# PicoInterface.net
KiCad netlist of a schematic drawn in Altium Designer
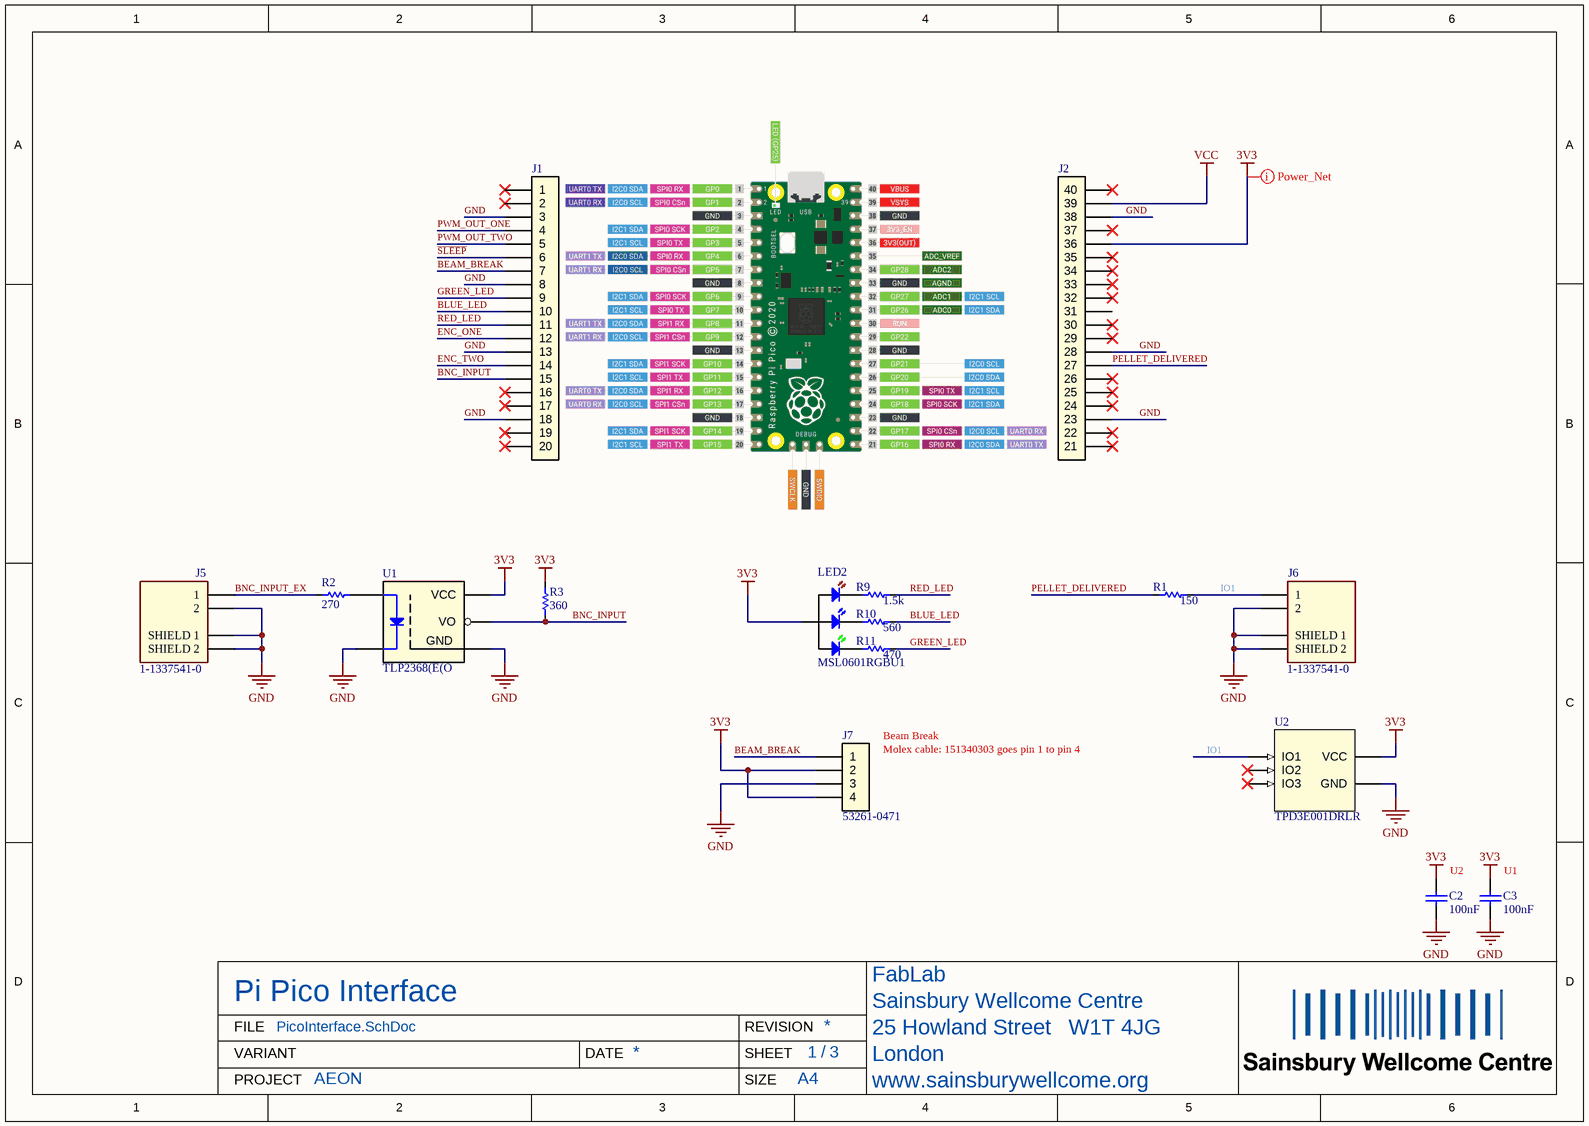
[diagram p0: PicoInterface.SchDoc]

(export (version "E")
  (design (tool "Eeschema 10.0.6"))
  (components
    (comp (ref "C2")
      (value "100nF")
      (footprint "FP-GRM188-0_1-e0_2_0_5-IPC_B")
      (description "0.1µF ±10% 100V Ceramic Capacitor X7R 0603 (1608 Metric)")
      (fields (field (name "VOLTAGE") "100V") (field (name "TOLERANCE") "10%"))
      (libsource (lib "Sainsbury Wellcome Centre") (part "Cap"))
    )
    (comp (ref "C3")
      (value "100nF")
      (footprint "FP-GRM188-0_1-e0_2_0_5-IPC_B")
      (description "0.1µF ±10% 100V Ceramic Capacitor X7R 0603 (1608 Metric)")
      (fields (field (name "VOLTAGE") "100V") (field (name "TOLERANCE") "10%"))
      (libsource (lib "Sainsbury Wellcome Centre") (part "Cap"))
    )
    (comp (ref "J1")
      (value "SSW-120-01-x-S")
      (footprint "SAMTEC_SSW-120-01-G-S")
      (description "Conn Socket Strip SKT 20 POS 2.54mm Solder ST Thru-Hole")
      (libsource (lib "Sainsbury Wellcome Centre") (part "Jack 20x1"))
    )
    (comp (ref "J2")
      (value "SSW-120-01-x-S - 21-40")
      (footprint "SAMTEC_SSW-120-01-G-S - 21-40")
      (description "Conn Socket Strip SKT 20 POS 2.54mm Solder ST Thru-Hole (pins 21 - 40)")
      (libsource (lib "Sainsbury Wellcome Centre") (part "Jack 20x1 21-40"))
    )
    (comp (ref "J5")
      (value "1-1337541-0")
      (footprint "TE- 1-1337541-0")
      (fields (field (name "PARTNUMBER") "1-1337541-0"))
      (libsource (lib "Sainsbury Wellcome Centre") (part "TE-1-1337541-0"))
    )
    (comp (ref "J6")
      (value "1-1337541-0")
      (footprint "TE- 1-1337541-0")
      (fields (field (name "PARTNUMBER") "1-1337541-0"))
      (libsource (lib "") (part "TE-1-1337541-0_1"))
    )
    (comp (ref "J7")
      (value "53261-0471")
      (footprint "MOLEX_53261-0471")
      (description "MOLEX 1.25mm (.049\") Pitch PicoBlade Header, Surface Mount, Right Angle, Lead-free, 4 Circuits")
      (libsource (lib "Sainsbury Wellcome Centre") (part "Jack 4x1"))
    )
    (comp (ref "LED2")
      (value "MSL0601RGBU1")
      (footprint "LED_MSL06_ROM")
      (description "Triple Color LED, Red/green/blue, Milky White")
      (fields (field (name "PARTNUMBER") "MSL0601RGBU1"))
      (libsource (lib "Sainsbury Wellcome Centre") (part "LED-RGB"))
    )
    (comp (ref "R1")
      (value "150")
      (footprint "FP-CPF0603-IPC_B")
      (description "Surface Mount Resistor 150 Ohm 1/16 W 0.1% 0603 (1608 Metric)")
      (fields (field (name "TOLERANCE") "0.1%") (field (name "Comment") "R0603-150R-1/16W-0.1%"))
      (libsource (lib "Sainsbury Wellcome Centre") (part "Res"))
    )
    (comp (ref "R2")
      (value "270")
      (footprint "FP-CPF0603-IPC_B")
      (description "Surface Mount Resistor 270 Ohm 1/16 W 0.1% 0603 (1608 Metric)")
      (fields (field (name "TOLERANCE") "0.1%") (field (name "Comment") "R0603-270R-1/16W-0.1%"))
      (libsource (lib "Sainsbury Wellcome Centre") (part "Res"))
    )
    (comp (ref "R3")
      (value "360")
      (footprint "FP-CPF0603-IPC_B")
      (description "Surface Mount Resistor 360 Ohm 1/16 W 0.1% 0603 (1608 Metric)")
      (fields (field (name "TOLERANCE") "0.1%") (field (name "Comment") "R0603-360R-1/16W-0.1%"))
      (libsource (lib "Sainsbury Wellcome Centre") (part "Res"))
    )
    (comp (ref "R9")
      (value "1.5k")
      (footprint "FP-CPF0603-IPC_B")
      (description "Surface Mount Resistor 1k5 Ohm 1/16 W 0.1% 0603 (1608 Metric)")
      (fields (field (name "TOLERANCE") "0.1%") (field (name "Comment") "R0603-1k5-1/16W-0.1%"))
      (libsource (lib "Sainsbury Wellcome Centre") (part "Res"))
    )
    (comp (ref "R10")
      (value "560")
      (footprint "FP-CPF0603-IPC_B")
      (description "Surface Mount Resistor 560 Ohm 1/16 W 0.1% 0603 (1608 Metric)")
      (fields (field (name "TOLERANCE") "0.1%") (field (name "Comment") "R0603-560R-1/16W-0.1%"))
      (libsource (lib "Sainsbury Wellcome Centre") (part "Res"))
    )
    (comp (ref "R11")
      (value "470")
      (footprint "FP-CPF0603-IPC_B")
      (description "Surface Mount Resistor 470 Ohm 1/16 W 0.1% 0603 (1608 Metric)")
      (fields (field (name "TOLERANCE") "0.1%") (field (name "Comment") "R0603-470R-1/16W-0.1%"))
      (libsource (lib "Sainsbury Wellcome Centre") (part "Res"))
    )
    (comp (ref "U1")
      (value "TLP2368")
      (footprint "5pin SO6_TOS")
      (fields (field (name "PARTNUMBER") "TLP2368(E(O"))
      (libsource (lib "Sainsbury Wellcome Centre") (part "TOS-TLP2368"))
    )
    (comp (ref "U2")
      (value "TPD3E001DRLR")
      (footprint "DRL5_TEX")
      (description "Low-Capacitance 3-Channel +/-15KV ESD-Protection Array for High-Speed Data Interfaces 5-SOT-5X3")
      (fields (field (name "PARTNUMBER") "TPD3E001DRLR"))
      (libsource (lib "Sainsbury Wellcome Centre") (part "TPD3E001DRLR"))
    )
  )
  (nets
    (net (code "1") (name "/BEAM_BREAK") (class "Default")
      (node (ref "J1") (pin "7") (pinfunction "7_7") (pintype "passive"))
      (node (ref "J7") (pin "1") (pinfunction "1_1") (pintype "passive"))
    )
    (net (code "2") (name "/BLUE_LED") (class "Default")
      (node (ref "J1") (pin "10") (pinfunction "10_10") (pintype "passive"))
      (node (ref "R10") (pin "2") (pinfunction "2_2") (pintype "passive"))
    )
    (net (code "3") (name "/BNC_INPUT") (class "Default")
      (node (ref "J1") (pin "15") (pinfunction "15_15") (pintype "passive"))
      (node (ref "R3") (pin "1") (pinfunction "1_1") (pintype "passive"))
      (node (ref "U1") (pin "5") (pinfunction "VO_5") (pintype "open_collector"))
    )
    (net (code "4") (name "/BNC_INPUT_EX") (class "Default")
      (node (ref "J5") (pin "1") (pinfunction "1_1") (pintype "passive"))
      (node (ref "R2") (pin "1") (pinfunction "1_1") (pintype "passive"))
    )
    (net (code "5") (name "/ENC_ONE") (class "Default")
      (node (ref "J1") (pin "12") (pinfunction "12_12") (pintype "passive"))
    )
    (net (code "6") (name "/ENC_TWO") (class "Default")
      (node (ref "J1") (pin "14") (pinfunction "14_14") (pintype "passive"))
    )
    (net (code "7") (name "/GREEN_LED") (class "Default")
      (node (ref "J1") (pin "9") (pinfunction "9_9") (pintype "passive"))
      (node (ref "R11") (pin "2") (pinfunction "2_2") (pintype "passive"))
    )
    (net (code "8") (name "/IO1") (class "Default")
      (node (ref "J6") (pin "1") (pinfunction "1_1") (pintype "passive"))
      (node (ref "R1") (pin "2") (pinfunction "2_2") (pintype "passive"))
      (node (ref "U2") (pin "1") (pinfunction "IO1_1") (pintype "input"))
    )
    (net (code "9") (name "/PELLET_DELIVERED") (class "Default")
      (node (ref "J2") (pin "27") (pinfunction "27_27") (pintype "passive"))
      (node (ref "R1") (pin "1") (pinfunction "1_1") (pintype "passive"))
    )
    (net (code "10") (name "/PWM_OUT_ONE") (class "Default")
      (node (ref "J1") (pin "4") (pinfunction "4_4") (pintype "passive"))
    )
    (net (code "11") (name "/PWM_OUT_TWO") (class "Default")
      (node (ref "J1") (pin "5") (pinfunction "5_5") (pintype "passive"))
    )
    (net (code "12") (name "/RED_LED") (class "Default")
      (node (ref "J1") (pin "11") (pinfunction "11_11") (pintype "passive"))
      (node (ref "R9") (pin "2") (pinfunction "2_2") (pintype "passive"))
    )
    (net (code "13") (name "/SLEEP") (class "Default")
      (node (ref "J1") (pin "6") (pinfunction "6_6") (pintype "passive"))
    )
    (net (code "14") (name "3V3") (class "Default")
      (node (ref "C2") (pin "2") (pinfunction "2_2") (pintype "passive"))
      (node (ref "C3") (pin "2") (pinfunction "2_2") (pintype "passive"))
      (node (ref "J2") (pin "36") (pinfunction "36_36") (pintype "passive"))
      (node (ref "J7") (pin "2") (pinfunction "2_2") (pintype "passive"))
      (node (ref "J7") (pin "4") (pinfunction "4_4") (pintype "passive"))
      (node (ref "LED2") (pin "1") (pinfunction "1_1") (pintype "passive"))
      (node (ref "R3") (pin "2") (pinfunction "2_2") (pintype "passive"))
      (node (ref "U1") (pin "6") (pinfunction "VCC_6") (pintype "power_in"))
      (node (ref "U2") (pin "5") (pinfunction "VCC_5") (pintype "power_in"))
    )
    (net (code "15") (name "GND") (class "Default")
      (node (ref "C2") (pin "1") (pinfunction "1_1") (pintype "passive"))
      (node (ref "C3") (pin "1") (pinfunction "1_1") (pintype "passive"))
      (node (ref "J1") (pin "13") (pinfunction "13_13") (pintype "passive"))
      (node (ref "J1") (pin "18") (pinfunction "18_18") (pintype "passive"))
      (node (ref "J1") (pin "3") (pinfunction "3_3") (pintype "passive"))
      (node (ref "J1") (pin "8") (pinfunction "8_8") (pintype "passive"))
      (node (ref "J2") (pin "23") (pinfunction "23_23") (pintype "passive"))
      (node (ref "J2") (pin "28") (pinfunction "28_28") (pintype "passive"))
      (node (ref "J2") (pin "38") (pinfunction "38_38") (pintype "passive"))
      (node (ref "J5") (pin "2") (pinfunction "2_2") (pintype "passive"))
      (node (ref "J5") (pin "SH1") (pinfunction "SHIELD_1_SH1") (pintype "passive"))
      (node (ref "J5") (pin "SH2") (pinfunction "SHIELD_2_SH2") (pintype "passive"))
      (node (ref "J6") (pin "2") (pinfunction "2_2") (pintype "passive"))
      (node (ref "J6") (pin "SH1") (pinfunction "SHIELD_1_SH1") (pintype "passive"))
      (node (ref "J6") (pin "SH2") (pinfunction "SHIELD_2_SH2") (pintype "passive"))
      (node (ref "J7") (pin "3") (pinfunction "3_3") (pintype "passive"))
      (node (ref "U1") (pin "3") (pinfunction "CATHODE_3") (pintype "passive"))
      (node (ref "U1") (pin "4") (pinfunction "GND_4") (pintype "passive"))
      (node (ref "U2") (pin "3") (pinfunction "GND_3") (pintype "power_in"))
    )
    (net (code "16") (name "Net-(LED2-Pad2)") (class "Default")
      (node (ref "LED2") (pin "2") (pinfunction "2_2") (pintype "passive"))
      (node (ref "R11") (pin "1") (pinfunction "1_1") (pintype "passive"))
    )
    (net (code "17") (name "Net-(LED2-Pad3)") (class "Default")
      (node (ref "LED2") (pin "3") (pinfunction "3_3") (pintype "passive"))
      (node (ref "R10") (pin "1") (pinfunction "1_1") (pintype "passive"))
    )
    (net (code "18") (name "Net-(LED2-Pad4)") (class "Default")
      (node (ref "LED2") (pin "4") (pinfunction "4_4") (pintype "passive"))
      (node (ref "R9") (pin "1") (pinfunction "1_1") (pintype "passive"))
    )
    (net (code "19") (name "Net-(U1-ANODE)") (class "Default")
      (node (ref "R2") (pin "2") (pinfunction "2_2") (pintype "passive"))
      (node (ref "U1") (pin "1") (pinfunction "ANODE_1") (pintype "passive"))
    )
    (net (code "20") (name "VCC") (class "Default")
      (node (ref "J2") (pin "39") (pinfunction "39_39") (pintype "passive"))
    )
    (net (code "21") (name "unconnected-(J1-Pad1)") (class "Default")
      (node (ref "J1") (pin "1") (pinfunction "1_1") (pintype "passive+no_connect"))
    )
    (net (code "22") (name "unconnected-(J1-Pad2)") (class "Default")
      (node (ref "J1") (pin "2") (pinfunction "2_2") (pintype "passive+no_connect"))
    )
    (net (code "23") (name "unconnected-(J1-Pad16)") (class "Default")
      (node (ref "J1") (pin "16") (pinfunction "16_16") (pintype "passive+no_connect"))
    )
    (net (code "24") (name "unconnected-(J1-Pad17)") (class "Default")
      (node (ref "J1") (pin "17") (pinfunction "17_17") (pintype "passive+no_connect"))
    )
    (net (code "25") (name "unconnected-(J1-Pad19)") (class "Default")
      (node (ref "J1") (pin "19") (pinfunction "19_19") (pintype "passive+no_connect"))
    )
    (net (code "26") (name "unconnected-(J1-Pad20)") (class "Default")
      (node (ref "J1") (pin "20") (pinfunction "20_20") (pintype "passive+no_connect"))
    )
    (net (code "27") (name "unconnected-(J2-Pad21)") (class "Default")
      (node (ref "J2") (pin "21") (pinfunction "21_21") (pintype "passive+no_connect"))
    )
    (net (code "28") (name "unconnected-(J2-Pad22)") (class "Default")
      (node (ref "J2") (pin "22") (pinfunction "22_22") (pintype "passive+no_connect"))
    )
    (net (code "29") (name "unconnected-(J2-Pad24)") (class "Default")
      (node (ref "J2") (pin "24") (pinfunction "24_24") (pintype "passive+no_connect"))
    )
    (net (code "30") (name "unconnected-(J2-Pad25)") (class "Default")
      (node (ref "J2") (pin "25") (pinfunction "25_25") (pintype "passive+no_connect"))
    )
    (net (code "31") (name "unconnected-(J2-Pad26)") (class "Default")
      (node (ref "J2") (pin "26") (pinfunction "26_26") (pintype "passive+no_connect"))
    )
    (net (code "32") (name "unconnected-(J2-Pad29)") (class "Default")
      (node (ref "J2") (pin "29") (pinfunction "29_29") (pintype "passive+no_connect"))
    )
    (net (code "33") (name "unconnected-(J2-Pad30)") (class "Default")
      (node (ref "J2") (pin "30") (pinfunction "30_30") (pintype "passive+no_connect"))
    )
    (net (code "34") (name "unconnected-(J2-Pad31)") (class "Default")
      (node (ref "J2") (pin "31") (pinfunction "31_31") (pintype "passive"))
    )
    (net (code "35") (name "unconnected-(J2-Pad32)") (class "Default")
      (node (ref "J2") (pin "32") (pinfunction "32_32") (pintype "passive+no_connect"))
    )
    (net (code "36") (name "unconnected-(J2-Pad33)") (class "Default")
      (node (ref "J2") (pin "33") (pinfunction "33_33") (pintype "passive+no_connect"))
    )
    (net (code "37") (name "unconnected-(J2-Pad34)") (class "Default")
      (node (ref "J2") (pin "34") (pinfunction "34_34") (pintype "passive+no_connect"))
    )
    (net (code "38") (name "unconnected-(J2-Pad35)") (class "Default")
      (node (ref "J2") (pin "35") (pinfunction "35_35") (pintype "passive+no_connect"))
    )
    (net (code "39") (name "unconnected-(J2-Pad37)") (class "Default")
      (node (ref "J2") (pin "37") (pinfunction "37_37") (pintype "passive+no_connect"))
    )
    (net (code "40") (name "unconnected-(J2-Pad40)") (class "Default")
      (node (ref "J2") (pin "40") (pinfunction "40_40") (pintype "passive+no_connect"))
    )
    (net (code "41") (name "unconnected-(U2-IO2-Pad2)") (class "Default")
      (node (ref "U2") (pin "2") (pinfunction "IO2_2") (pintype "input+no_connect"))
    )
    (net (code "42") (name "unconnected-(U2-IO3-Pad4)") (class "Default")
      (node (ref "U2") (pin "4") (pinfunction "IO3_4") (pintype "input+no_connect"))
    )
  )
)
